# control.net
KiCad netlist of a schematic drawn in EAGLE
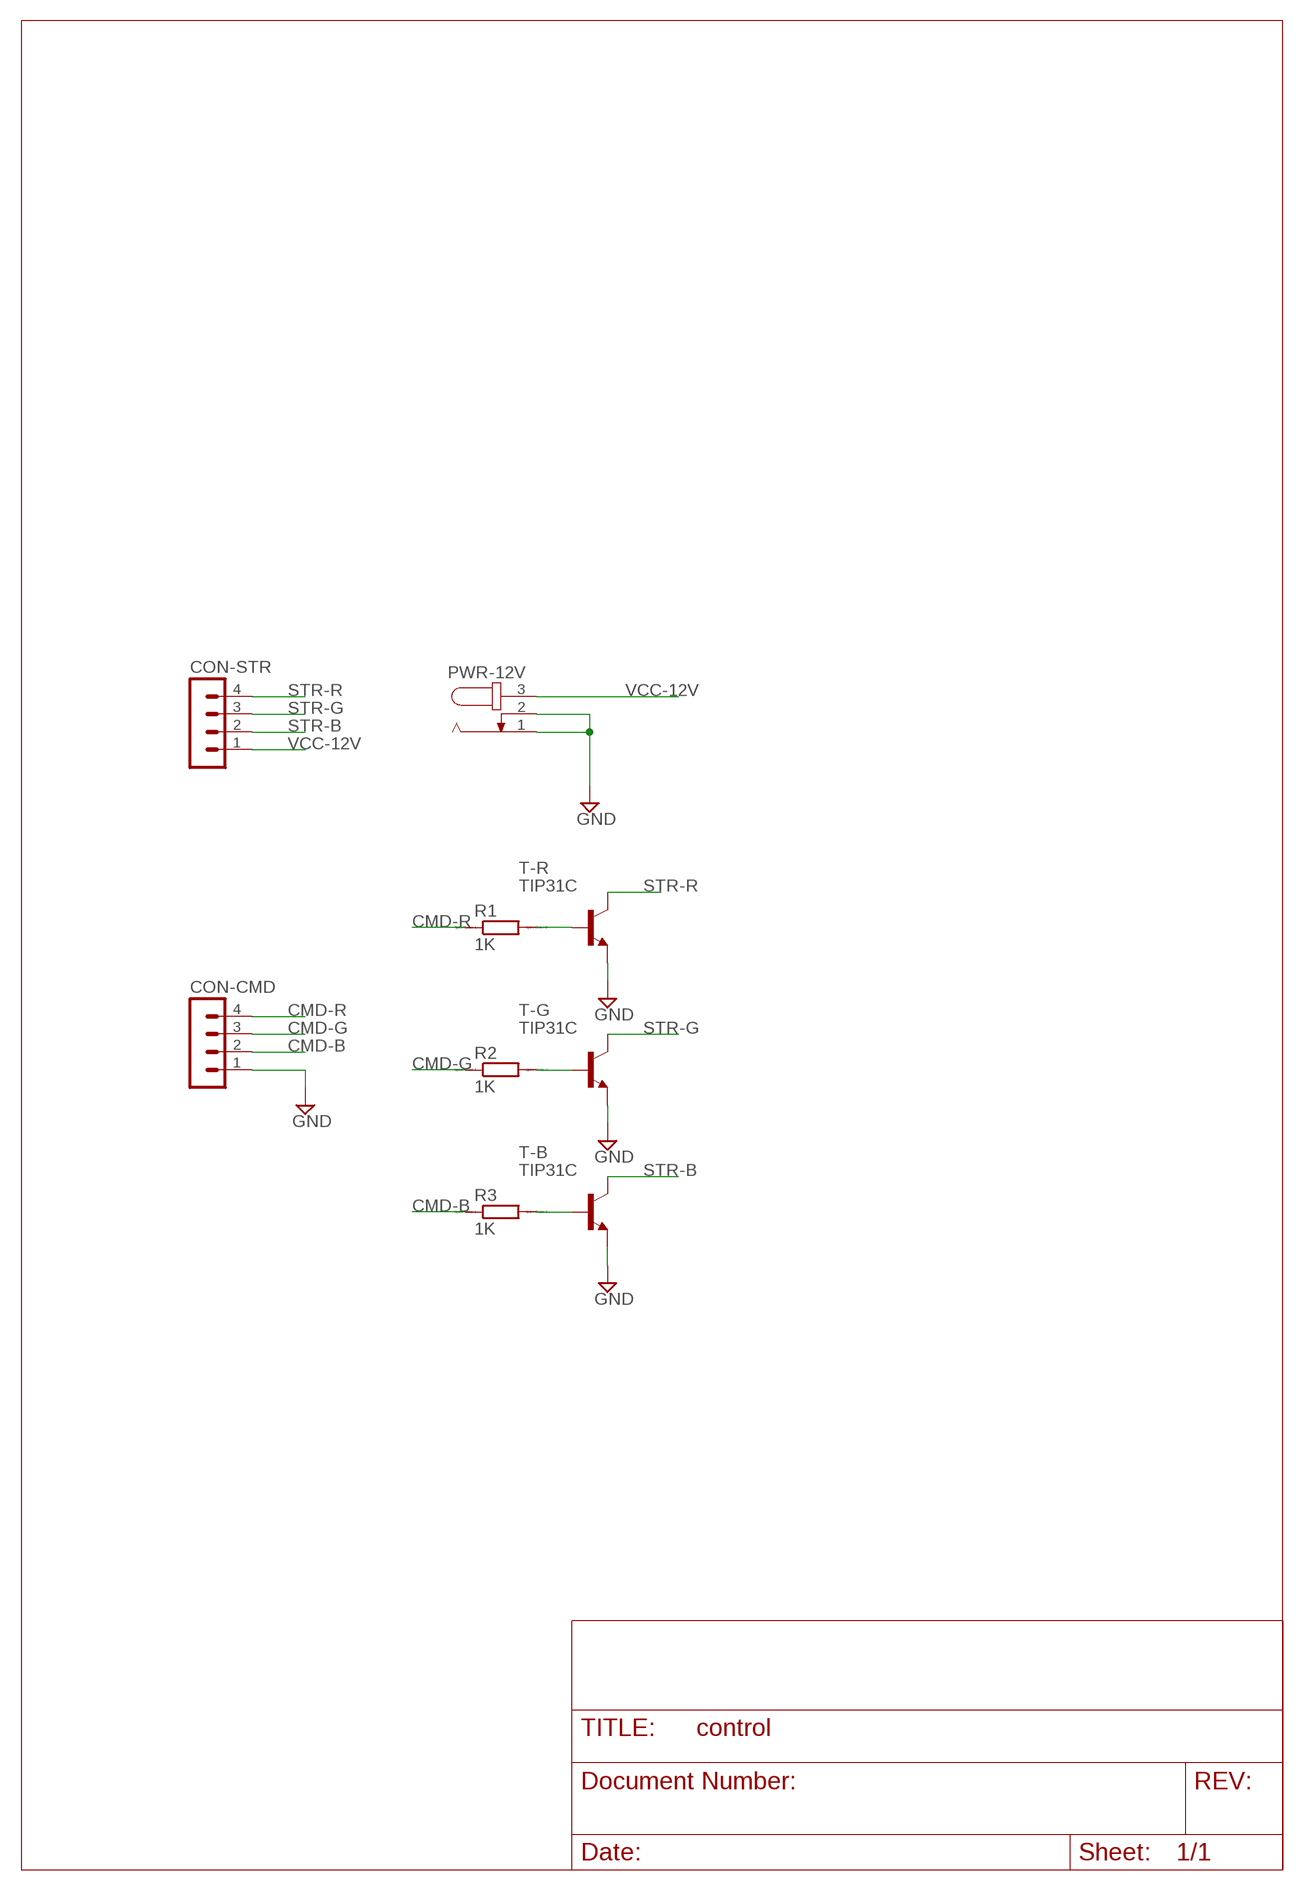
[diagram p0: schematic, sheet 1]

(export (version "E")
  (design (tool "Eeschema 10.0.6"))
  (components
    (comp (ref "CON-CMD")
      (value "MA04-1")
      (footprint "eagle-import:MA04-1")
      (libsource (lib "eagle-import") (part "MA04-1"))
    )
    (comp (ref "CON-STR")
      (value "MA04-1")
      (footprint "eagle-import:MA04-1")
      (libsource (lib "eagle-import") (part "MA04-1"))
    )
    (comp (ref "PWR-12V")
      (value "JACK-PLUG0")
      (footprint "eagle-import:SPC4077")
      (libsource (lib "eagle-import") (part "JACK-PLUG0"))
    )
    (comp (ref "R1")
      (value "1K")
      (footprint "eagle-import:0207_10")
      (libsource (lib "eagle-import") (part "R0207/10"))
    )
    (comp (ref "R2")
      (value "1K")
      (footprint "eagle-import:0207_10")
      (libsource (lib "eagle-import") (part "R0207/10"))
    )
    (comp (ref "R3")
      (value "1K")
      (footprint "eagle-import:0207_10")
      (libsource (lib "eagle-import") (part "R0207/10"))
    )
    (comp (ref "T-B")
      (value "TIP31C")
      (footprint "eagle-import:TO220")
      (libsource (lib "eagle-import") (part "TIP31C"))
    )
    (comp (ref "T-G")
      (value "TIP31C")
      (footprint "eagle-import:TO220")
      (libsource (lib "eagle-import") (part "TIP31C"))
    )
    (comp (ref "T-R")
      (value "TIP31C")
      (footprint "eagle-import:TO220")
      (libsource (lib "eagle-import") (part "TIP31C"))
    )
  )
  (nets
    (net (code "1") (name "/CMD-B") (class "Default")
      (node (ref "CON-CMD") (pin "2") (pinfunction "2_2") (pintype "passive"))
      (node (ref "R3") (pin "1") (pinfunction "1_1") (pintype "passive"))
    )
    (net (code "2") (name "/CMD-G") (class "Default")
      (node (ref "CON-CMD") (pin "3") (pinfunction "3_3") (pintype "passive"))
      (node (ref "R2") (pin "1") (pinfunction "1_1") (pintype "passive"))
    )
    (net (code "3") (name "/CMD-R") (class "Default")
      (node (ref "CON-CMD") (pin "4") (pinfunction "4_4") (pintype "passive"))
      (node (ref "R1") (pin "1") (pinfunction "1_1") (pintype "passive"))
    )
    (net (code "4") (name "/STR-B") (class "Default")
      (node (ref "CON-STR") (pin "2") (pinfunction "2_2") (pintype "passive"))
      (node (ref "T-B") (pin "2") (pinfunction "C_2") (pintype "passive"))
    )
    (net (code "5") (name "/STR-G") (class "Default")
      (node (ref "CON-STR") (pin "3") (pinfunction "3_3") (pintype "passive"))
      (node (ref "T-G") (pin "2") (pinfunction "C_2") (pintype "passive"))
    )
    (net (code "6") (name "/STR-R") (class "Default")
      (node (ref "CON-STR") (pin "4") (pinfunction "4_4") (pintype "passive"))
      (node (ref "T-R") (pin "2") (pinfunction "C_2") (pintype "passive"))
    )
    (net (code "7") (name "/VCC-12V") (class "Default")
      (node (ref "CON-STR") (pin "1") (pinfunction "1_1") (pintype "passive"))
      (node (ref "PWR-12V") (pin "3") (pinfunction "3_3") (pintype "passive"))
    )
    (net (code "8") (name "GND") (class "Default")
      (node (ref "CON-CMD") (pin "1") (pinfunction "1_1") (pintype "passive"))
      (node (ref "PWR-12V") (pin "1") (pinfunction "1_1") (pintype "passive"))
      (node (ref "PWR-12V") (pin "2") (pinfunction "2_2") (pintype "passive"))
      (node (ref "T-B") (pin "3") (pinfunction "E_3") (pintype "passive"))
      (node (ref "T-G") (pin "3") (pinfunction "E_3") (pintype "passive"))
      (node (ref "T-R") (pin "3") (pinfunction "E_3") (pintype "passive"))
    )
    (net (code "9") (name "Net-(T-B-B)") (class "Default")
      (node (ref "R3") (pin "2") (pinfunction "2_2") (pintype "passive"))
      (node (ref "T-B") (pin "1") (pinfunction "B_1") (pintype "passive"))
    )
    (net (code "10") (name "Net-(T-G-B)") (class "Default")
      (node (ref "R2") (pin "2") (pinfunction "2_2") (pintype "passive"))
      (node (ref "T-G") (pin "1") (pinfunction "B_1") (pintype "passive"))
    )
    (net (code "11") (name "Net-(T-R-B)") (class "Default")
      (node (ref "R1") (pin "2") (pinfunction "2_2") (pintype "passive"))
      (node (ref "T-R") (pin "1") (pinfunction "B_1") (pintype "passive"))
    )
  )
)
